# EEPROM.net
KiCad netlist of a schematic drawn in Altium Designer
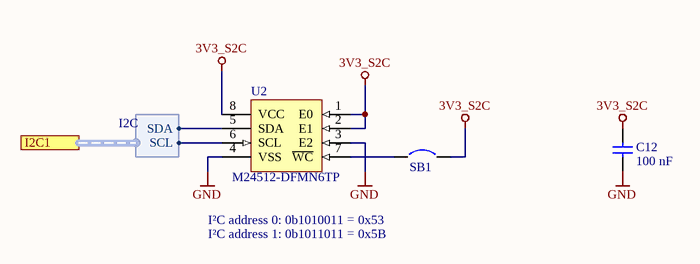
[diagram p0: EEPROM.SchDoc]

(export (version "E")
  (design (tool "Eeschema 10.0.6"))
  (components
    (comp (ref "C12")
      (value "100 nF")
      (footprint "C_0603_TE")
      (description "Generic capacitor")
      (fields
        (field (name "TOLERANCE") "10 %")
        (field (name "MANUFACTURER PART NUMBER") "UZgen_C_0603_100nF_50V_X7R")
        (field (name "CREATED FROM") "AGeiger")
      )
      (libsource (lib "user") (part "CAP-NP"))
    )
    (comp (ref "SB1")
      (value "Solder Bump 0603")
      (footprint "SB_0603")
      (fields (field (name "CREATED FROM") "AGeiger"))
      (libsource (lib "user") (part "Solder_Bump"))
    )
    (comp (ref "U2")
      (value "M24512-DFMN6TP")
      (footprint "D0008A_N")
      (description "512Kbit 1MHz I2C SOP-8 EEPROM ROHS")
      (fields
        (field (name "MANUFACTURER") "STMicroelectronics")
        (field (name "LCSC PART NUMBER") "C222090")
        (field (name "CREATED FROM") "FRosner")
      )
      (libsource (lib "user") (part "M24256"))
    )
  )
  (nets
    (net (code "2") (name "/SCL") (class "Default")
      (node (ref "U2") (pin "6") (pinfunction "SCL_6") (pintype "input"))
    )
    (net (code "3") (name "/SDA") (class "Default")
      (node (ref "U2") (pin "5") (pinfunction "SDA_5") (pintype "open_collector"))
    )
    (net (code "5") (name "3V3_S2C") (class "Default")
      (node (ref "C12") (pin "1") (pinfunction "1_1") (pintype "passive"))
      (node (ref "SB1") (pin "2") (pinfunction "2_2") (pintype "passive"))
      (node (ref "U2") (pin "1") (pinfunction "E0_1") (pintype "input"))
      (node (ref "U2") (pin "2") (pinfunction "E1_2") (pintype "input"))
      (node (ref "U2") (pin "8") (pinfunction "VCC_8") (pintype "power_in"))
    )
    (net (code "6") (name "GND") (class "Default")
      (node (ref "C12") (pin "2") (pinfunction "2_2") (pintype "passive"))
      (node (ref "U2") (pin "3") (pinfunction "E2_3") (pintype "input"))
      (node (ref "U2") (pin "4") (pinfunction "VSS_4") (pintype "power_in"))
    )
    (net (code "7") (name "Net-(U2-~{WC})") (class "Default")
      (node (ref "SB1") (pin "1") (pinfunction "1_1") (pintype "passive"))
      (node (ref "U2") (pin "7") (pinfunction "~{WC}_7") (pintype "input"))
    )
  )
)
